# board2side_small.net
KiCad netlist of a schematic drawn in EAGLE
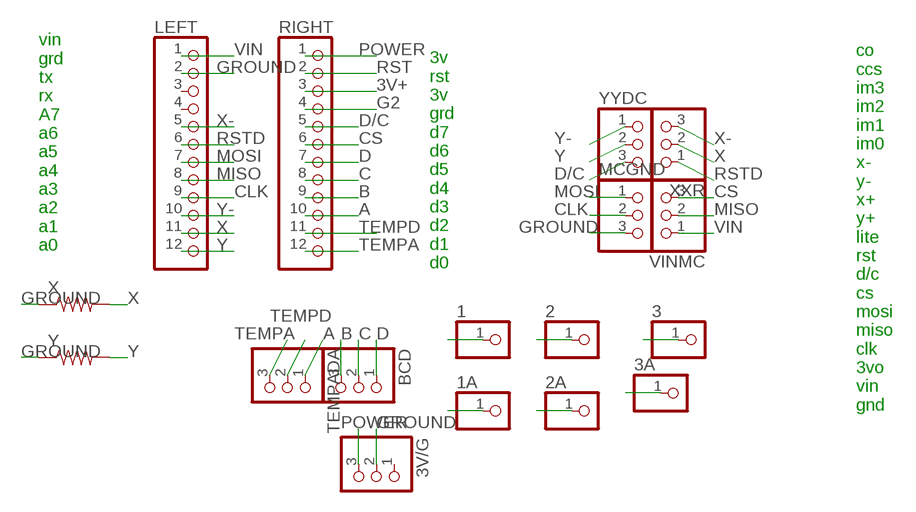
[diagram p0: schematic, sheet 1]

(export (version "E")
  (design (tool "Eeschema 10.0.6"))
  (components
    (comp (ref "1")
      (value "PINHD-1X1CB")
      (footprint "eagle-import:1X01-CLEANBIG")
      (libsource (lib "eagle-import") (part "PINHD-1X1CB"))
    )
    (comp (ref "1A")
      (value "PINHD-1X1CB")
      (footprint "eagle-import:1X01-CLEANBIG")
      (libsource (lib "eagle-import") (part "PINHD-1X1CB"))
    )
    (comp (ref "2")
      (value "PINHD-1X1CB")
      (footprint "eagle-import:1X01-CLEANBIG")
      (libsource (lib "eagle-import") (part "PINHD-1X1CB"))
    )
    (comp (ref "2A")
      (value "PINHD-1X1CB")
      (footprint "eagle-import:1X01-CLEANBIG")
      (libsource (lib "eagle-import") (part "PINHD-1X1CB"))
    )
    (comp (ref "3")
      (value "PINHD-1X1CB")
      (footprint "eagle-import:1X01-CLEANBIG")
      (libsource (lib "eagle-import") (part "PINHD-1X1CB"))
    )
    (comp (ref "3A")
      (value "PINHD-1X1CB")
      (footprint "eagle-import:1X01-CLEANBIG")
      (libsource (lib "eagle-import") (part "PINHD-1X1CB"))
    )
    (comp (ref "3V/G")
      (value "PINHD-1X3CB")
      (footprint "eagle-import:1X03-CLEANBIG")
      (libsource (lib "eagle-import") (part "PINHD-1X3CB"))
    )
    (comp (ref "BCD")
      (value "PINHD-1X3CB")
      (footprint "eagle-import:1X03-CLEANBIG")
      (libsource (lib "eagle-import") (part "PINHD-1X3CB"))
    )
    (comp (ref "LEFT")
      (value "PINHD-1X12-CB")
      (footprint "eagle-import:1X12-CB")
      (libsource (lib "eagle-import") (part "PINHD-1X12-CB"))
    )
    (comp (ref "MCGND")
      (value "PINHD-1X3CB")
      (footprint "eagle-import:1X03-CLEANBIG")
      (libsource (lib "eagle-import") (part "PINHD-1X3CB"))
    )
    (comp (ref "RIGHT")
      (value "PINHD-1X12-CB")
      (footprint "eagle-import:1X12-CB")
      (libsource (lib "eagle-import") (part "PINHD-1X12-CB"))
    )
    (comp (ref "TEMPADA")
      (value "PINHD-1X3CB")
      (footprint "eagle-import:1X03-CLEANBIG")
      (libsource (lib "eagle-import") (part "PINHD-1X3CB"))
    )
    (comp (ref "VINMC")
      (value "PINHD-1X3CB")
      (footprint "eagle-import:1X03-CLEANBIG")
      (libsource (lib "eagle-import") (part "PINHD-1X3CB"))
    )
    (comp (ref "X")
      (value "10KOHM-1/6W-5%(PTH)KIT")
      (footprint "eagle-import:AXIAL-0.3-KIT")
      (libsource (lib "eagle-import") (part "10KOHM-1/6W-5%(PTH)KIT"))
    )
    (comp (ref "XXR")
      (value "PINHD-1X3CB")
      (footprint "eagle-import:1X03-CLEANBIG")
      (libsource (lib "eagle-import") (part "PINHD-1X3CB"))
    )
    (comp (ref "Y")
      (value "10KOHM-1/6W-5%(PTH)KIT")
      (footprint "eagle-import:AXIAL-0.3-KIT")
      (libsource (lib "eagle-import") (part "10KOHM-1/6W-5%(PTH)KIT"))
    )
    (comp (ref "YYDC")
      (value "PINHD-1X3CB")
      (footprint "eagle-import:1X03-CLEANBIG")
      (libsource (lib "eagle-import") (part "PINHD-1X3CB"))
    )
  )
  (nets
    (net (code "1") (name "/1") (class "Default")
      (node (ref "1") (pin "1") (pinfunction "1_1") (pintype "passive"))
      (node (ref "1A") (pin "1") (pinfunction "1_1") (pintype "passive"))
    )
    (net (code "2") (name "/2") (class "Default")
      (node (ref "2") (pin "1") (pinfunction "1_1") (pintype "passive"))
      (node (ref "2A") (pin "1") (pinfunction "1_1") (pintype "passive"))
    )
    (net (code "3") (name "/3") (class "Default")
      (node (ref "3") (pin "1") (pinfunction "1_1") (pintype "passive"))
      (node (ref "3A") (pin "1") (pinfunction "1_1") (pintype "passive"))
    )
    (net (code "4") (name "/3V+") (class "Default")
      (node (ref "RIGHT") (pin "3") (pinfunction "3_3") (pintype "passive"))
    )
    (net (code "5") (name "/A") (class "Default")
      (node (ref "RIGHT") (pin "10") (pinfunction "10_10") (pintype "passive"))
      (node (ref "TEMPADA") (pin "1") (pinfunction "1_1") (pintype "passive"))
    )
    (net (code "6") (name "/B") (class "Default")
      (node (ref "BCD") (pin "3") (pinfunction "3_3") (pintype "passive"))
      (node (ref "RIGHT") (pin "9") (pinfunction "9_9") (pintype "passive"))
    )
    (net (code "7") (name "/C") (class "Default")
      (node (ref "BCD") (pin "2") (pinfunction "2_2") (pintype "passive"))
      (node (ref "RIGHT") (pin "8") (pinfunction "8_8") (pintype "passive"))
    )
    (net (code "8") (name "/CLK") (class "Default")
      (node (ref "LEFT") (pin "9") (pinfunction "9_9") (pintype "passive"))
      (node (ref "MCGND") (pin "2") (pinfunction "2_2") (pintype "passive"))
    )
    (net (code "9") (name "/CS") (class "Default")
      (node (ref "RIGHT") (pin "6") (pinfunction "6_6") (pintype "passive"))
      (node (ref "VINMC") (pin "3") (pinfunction "3_3") (pintype "passive"))
    )
    (net (code "10") (name "/D") (class "Default")
      (node (ref "BCD") (pin "1") (pinfunction "1_1") (pintype "passive"))
      (node (ref "RIGHT") (pin "7") (pinfunction "7_7") (pintype "passive"))
    )
    (net (code "11") (name "/D{slash}C") (class "Default")
      (node (ref "RIGHT") (pin "5") (pinfunction "5_5") (pintype "passive"))
      (node (ref "YYDC") (pin "3") (pinfunction "3_3") (pintype "passive"))
    )
    (net (code "12") (name "/G2") (class "Default")
      (node (ref "RIGHT") (pin "4") (pinfunction "4_4") (pintype "passive"))
    )
    (net (code "13") (name "/GROUND") (class "Default")
      (node (ref "3V/G") (pin "2") (pinfunction "2_2") (pintype "passive"))
      (node (ref "LEFT") (pin "2") (pinfunction "2_2") (pintype "passive"))
      (node (ref "MCGND") (pin "3") (pinfunction "3_3") (pintype "passive"))
      (node (ref "X") (pin "P$1") (pinfunction "1_P$1") (pintype "passive"))
      (node (ref "Y") (pin "P$1") (pinfunction "1_P$1") (pintype "passive"))
    )
    (net (code "14") (name "/MISO") (class "Default")
      (node (ref "LEFT") (pin "8") (pinfunction "8_8") (pintype "passive"))
      (node (ref "VINMC") (pin "2") (pinfunction "2_2") (pintype "passive"))
    )
    (net (code "15") (name "/MOSI") (class "Default")
      (node (ref "LEFT") (pin "7") (pinfunction "7_7") (pintype "passive"))
      (node (ref "MCGND") (pin "1") (pinfunction "1_1") (pintype "passive"))
    )
    (net (code "16") (name "/POWER") (class "Default")
      (node (ref "3V/G") (pin "3") (pinfunction "3_3") (pintype "passive"))
      (node (ref "RIGHT") (pin "1") (pinfunction "1_1") (pintype "passive"))
    )
    (net (code "17") (name "/RST") (class "Default")
      (node (ref "RIGHT") (pin "2") (pinfunction "2_2") (pintype "passive"))
    )
    (net (code "18") (name "/RSTD") (class "Default")
      (node (ref "LEFT") (pin "6") (pinfunction "6_6") (pintype "passive"))
      (node (ref "XXR") (pin "1") (pinfunction "1_1") (pintype "passive"))
    )
    (net (code "19") (name "/TEMPA") (class "Default")
      (node (ref "RIGHT") (pin "12") (pinfunction "12_12") (pintype "passive"))
      (node (ref "TEMPADA") (pin "3") (pinfunction "3_3") (pintype "passive"))
    )
    (net (code "20") (name "/TEMPD") (class "Default")
      (node (ref "RIGHT") (pin "11") (pinfunction "11_11") (pintype "passive"))
      (node (ref "TEMPADA") (pin "2") (pinfunction "2_2") (pintype "passive"))
    )
    (net (code "21") (name "/VIN") (class "Default")
      (node (ref "LEFT") (pin "1") (pinfunction "1_1") (pintype "passive"))
      (node (ref "VINMC") (pin "1") (pinfunction "1_1") (pintype "passive"))
    )
    (net (code "22") (name "/X") (class "Default")
      (node (ref "LEFT") (pin "11") (pinfunction "11_11") (pintype "passive"))
      (node (ref "X") (pin "P$2") (pinfunction "2_P$2") (pintype "passive"))
      (node (ref "XXR") (pin "2") (pinfunction "2_2") (pintype "passive"))
    )
    (net (code "23") (name "/X-") (class "Default")
      (node (ref "LEFT") (pin "5") (pinfunction "5_5") (pintype "passive"))
      (node (ref "XXR") (pin "3") (pinfunction "3_3") (pintype "passive"))
    )
    (net (code "24") (name "/Y") (class "Default")
      (node (ref "LEFT") (pin "12") (pinfunction "12_12") (pintype "passive"))
      (node (ref "Y") (pin "P$2") (pinfunction "2_P$2") (pintype "passive"))
      (node (ref "YYDC") (pin "2") (pinfunction "2_2") (pintype "passive"))
    )
    (net (code "25") (name "/Y-") (class "Default")
      (node (ref "LEFT") (pin "10") (pinfunction "10_10") (pintype "passive"))
      (node (ref "YYDC") (pin "1") (pinfunction "1_1") (pintype "passive"))
    )
    (net (code "26") (name "unconnected-(3V/G-Pad1)") (class "Default")
      (node (ref "3V/G") (pin "1") (pinfunction "1_1") (pintype "passive"))
    )
    (net (code "27") (name "unconnected-(LEFT-Pad3)") (class "Default")
      (node (ref "LEFT") (pin "3") (pinfunction "3_3") (pintype "passive"))
    )
    (net (code "28") (name "unconnected-(LEFT-Pad4)") (class "Default")
      (node (ref "LEFT") (pin "4") (pinfunction "4_4") (pintype "passive"))
    )
  )
)
